# CONNECTOR_INTERFACE.net
KiCad netlist of a schematic drawn in Altium Designer
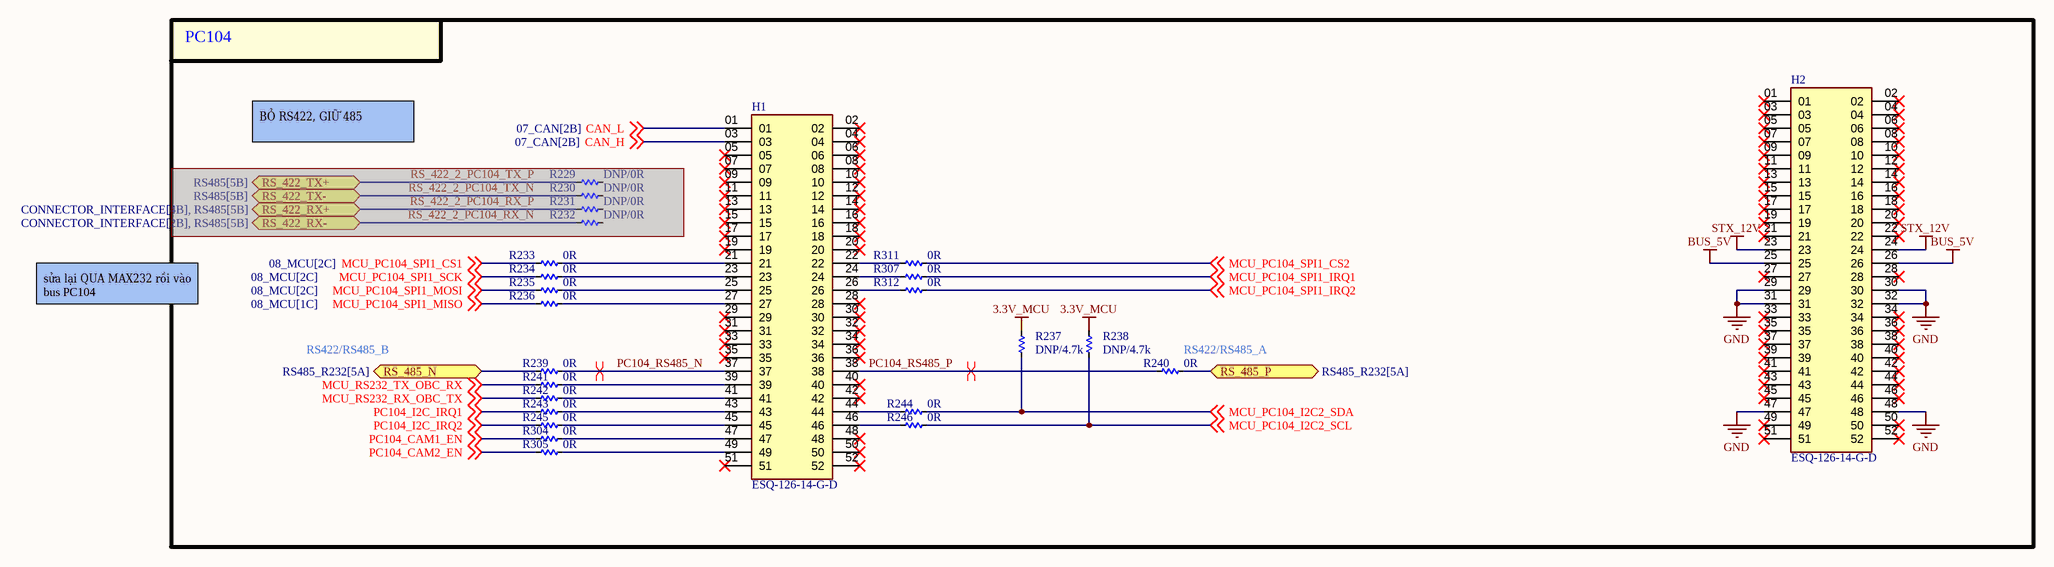
[diagram p0: CONNECTOR_INTERFACE.SchDoc]

(export (version "E")
  (design (tool "Eeschema 10.0.6"))
  (components
    (comp (ref "H1")
      (value "ESQ-126-14-G-D")
      (footprint "SAMTEC_ESQ-126-14-G-D")
      (description "CONN SOCKET 52POS 0.1 GOLD PCB")
      (fields (field (name "MF") "Samtec"))
      (libsource (lib "IFBschelib") (part "ESQ-126-14-G-D"))
    )
    (comp (ref "H2")
      (value "ESQ-126-14-G-D")
      (footprint "SAMTEC_ESQ-126-14-G-D")
      (description "CONN SOCKET 52POS 0.1 GOLD PCB")
      (fields (field (name "MF") "Samtec"))
      (libsource (lib "IFBschelib") (part "ESQ-126-14-G-D"))
    )
    (comp (ref "R229")
      (value "DNP/0R")
      (footprint "RES_C_1005x30_L")
      (description "RES")
      (libsource (lib "LABLIB") (part "_RES_B_2"))
    )
    (comp (ref "R230")
      (value "DNP/0R")
      (footprint "RES_C_1005x30_L")
      (description "RES")
      (libsource (lib "LABLIB") (part "_RES_B_2"))
    )
    (comp (ref "R231")
      (value "DNP/0R")
      (footprint "RES_C_1005x30_L")
      (description "RES")
      (libsource (lib "LABLIB") (part "_RES_B_2"))
    )
    (comp (ref "R232")
      (value "DNP/0R")
      (footprint "RES_C_1005x30_L")
      (description "RES")
      (libsource (lib "LABLIB") (part "_RES_B_2"))
    )
    (comp (ref "R233")
      (value "0R")
      (footprint "RES_C_1005x30_L")
      (description "RES")
      (libsource (lib "IFBschelib") (part "_RES_B_2"))
    )
    (comp (ref "R234")
      (value "0R")
      (footprint "RES_C_1005x30_L")
      (description "RES")
      (libsource (lib "IFBschelib") (part "_RES_B_2"))
    )
    (comp (ref "R235")
      (value "0R")
      (footprint "RES_C_1005x30_L")
      (description "RES")
      (libsource (lib "IFBschelib") (part "_RES_B_2"))
    )
    (comp (ref "R236")
      (value "0R")
      (footprint "RES_C_1005x30_L")
      (description "RES")
      (libsource (lib "IFBschelib") (part "_RES_B_2"))
    )
    (comp (ref "R237")
      (value "DNP/4.7k")
      (footprint "RES_C_1005x30_L")
      (description "RES")
      (libsource (lib "IFBschelib") (part "_RES_B_2"))
    )
    (comp (ref "R238")
      (value "DNP/4.7k")
      (footprint "RES_C_1005x30_L")
      (description "RES")
      (libsource (lib "IFBschelib") (part "_RES_B_2"))
    )
    (comp (ref "R239")
      (value "0R")
      (footprint "RES_C_1005x30_L")
      (description "RES")
      (libsource (lib "IFBschelib") (part "_RES_B_2"))
    )
    (comp (ref "R240")
      (value "0R")
      (footprint "RES_C_1005x30_L")
      (description "RES")
      (libsource (lib "IFBschelib") (part "_RES_B_2"))
    )
    (comp (ref "R241")
      (value "0R")
      (footprint "RES_C_1005x30_L")
      (description "RES")
      (libsource (lib "IFBschelib") (part "_RES_B_2"))
    )
    (comp (ref "R242")
      (value "0R")
      (footprint "RES_C_1005x30_L")
      (description "RES")
      (libsource (lib "IFBschelib") (part "_RES_B_2"))
    )
    (comp (ref "R243")
      (value "0R")
      (footprint "RES_C_1005x30_L")
      (description "RES")
      (libsource (lib "LABLIB") (part "_RES_B_2"))
    )
    (comp (ref "R244")
      (value "0R")
      (footprint "RES_C_1005x30_L")
      (description "RES")
      (libsource (lib "LABLIB") (part "_RES_B_2"))
    )
    (comp (ref "R245")
      (value "0R")
      (footprint "RES_C_1005x30_L")
      (description "RES")
      (libsource (lib "LABLIB") (part "_RES_B_2"))
    )
    (comp (ref "R246")
      (value "0R")
      (footprint "RES_C_1005x30_L")
      (description "RES")
      (libsource (lib "LABLIB") (part "_RES_B_2"))
    )
    (comp (ref "R304")
      (value "0R")
      (footprint "RES_C_1005x30_L")
      (description "RES")
      (libsource (lib "LABLIB") (part "_RES_B_2"))
    )
    (comp (ref "R305")
      (value "0R")
      (footprint "RES_C_1005x30_L")
      (description "RES")
      (libsource (lib "LABLIB") (part "_RES_B_2"))
    )
    (comp (ref "R307")
      (value "0R")
      (footprint "RES_C_1005x30_L")
      (description "RES")
      (libsource (lib "IFBschelib") (part "_RES_B_2"))
    )
    (comp (ref "R311")
      (value "0R")
      (footprint "RES_C_1005x30_L")
      (description "RES")
      (libsource (lib "IFBschelib") (part "_RES_B_2"))
    )
    (comp (ref "R312")
      (value "0R")
      (footprint "RES_C_1005x30_L")
      (description "RES")
      (libsource (lib "IFBschelib") (part "_RES_B_2"))
    )
  )
  (nets
    (net (code "1") (name "/PC104_RS485_N") (class "Default")
      (node (ref "H1") (pin "37") (pinfunction "37_37") (pintype "passive"))
      (node (ref "R239") (pin "2") (pinfunction "2_2") (pintype "passive"))
    )
    (net (code "2") (name "/PC104_RS485_P") (class "Default")
      (node (ref "H1") (pin "38") (pinfunction "38_38") (pintype "passive"))
      (node (ref "R240") (pin "1") (pinfunction "1_1") (pintype "passive"))
    )
    (net (code "3") (name "/RS_422_2_PC104_RX_N") (class "Default")
      (node (ref "R232") (pin "1") (pinfunction "1_1") (pintype "passive"))
    )
    (net (code "4") (name "/RS_422_2_PC104_RX_P") (class "Default")
      (node (ref "R231") (pin "1") (pinfunction "1_1") (pintype "passive"))
    )
    (net (code "5") (name "/RS_422_2_PC104_TX_N") (class "Default")
      (node (ref "R230") (pin "1") (pinfunction "1_1") (pintype "passive"))
    )
    (net (code "6") (name "/RS_422_2_PC104_TX_P") (class "Default")
      (node (ref "R229") (pin "1") (pinfunction "1_1") (pintype "passive"))
    )
    (net (code "7") (name "/RS_485_N") (class "Default")
      (node (ref "R239") (pin "1") (pinfunction "1_1") (pintype "passive"))
    )
    (net (code "8") (name "/RS_485_P") (class "Default")
      (node (ref "R240") (pin "2") (pinfunction "2_2") (pintype "passive"))
    )
    (net (code "9") (name "3.3V_MCU") (class "Default")
      (node (ref "R237") (pin "2") (pinfunction "2_2") (pintype "passive"))
      (node (ref "R238") (pin "2") (pinfunction "2_2") (pintype "passive"))
    )
    (net (code "10") (name "BUS_5V") (class "Default")
      (node (ref "H2") (pin "25") (pinfunction "25_25") (pintype "passive"))
      (node (ref "H2") (pin "26") (pinfunction "26_26") (pintype "passive"))
    )
    (net (code "11") (name "CAN_H") (class "Default")
      (node (ref "H1") (pin "03") (pinfunction "03_03") (pintype "passive"))
    )
    (net (code "12") (name "CAN_L") (class "Default")
      (node (ref "H1") (pin "01") (pinfunction "01_01") (pintype "passive"))
    )
    (net (code "13") (name "GND") (class "Default")
      (node (ref "H2") (pin "29") (pinfunction "29_29") (pintype "passive"))
      (node (ref "H2") (pin "30") (pinfunction "30_30") (pintype "passive"))
      (node (ref "H2") (pin "31") (pinfunction "31_31") (pintype "passive"))
      (node (ref "H2") (pin "32") (pinfunction "32_32") (pintype "passive"))
      (node (ref "H2") (pin "47") (pinfunction "47_47") (pintype "passive"))
      (node (ref "H2") (pin "48") (pinfunction "48_48") (pintype "passive"))
    )
    (net (code "14") (name "MCU_PC104_I2C2_SCL") (class "Default")
      (node (ref "R238") (pin "1") (pinfunction "1_1") (pintype "passive"))
      (node (ref "R246") (pin "2") (pinfunction "2_2") (pintype "passive"))
    )
    (net (code "15") (name "MCU_PC104_I2C2_SDA") (class "Default")
      (node (ref "R237") (pin "1") (pinfunction "1_1") (pintype "passive"))
      (node (ref "R244") (pin "2") (pinfunction "2_2") (pintype "passive"))
    )
    (net (code "16") (name "MCU_PC104_SPI1_CS1") (class "Default")
      (node (ref "R233") (pin "1") (pinfunction "1_1") (pintype "passive"))
    )
    (net (code "17") (name "MCU_PC104_SPI1_CS2") (class "Default")
      (node (ref "R311") (pin "1") (pinfunction "1_1") (pintype "passive"))
    )
    (net (code "18") (name "MCU_PC104_SPI1_IRQ1") (class "Default")
      (node (ref "R307") (pin "2") (pinfunction "2_2") (pintype "passive"))
    )
    (net (code "19") (name "MCU_PC104_SPI1_IRQ2") (class "Default")
      (node (ref "R312") (pin "2") (pinfunction "2_2") (pintype "passive"))
    )
    (net (code "20") (name "MCU_PC104_SPI1_MISO") (class "Default")
      (node (ref "R236") (pin "1") (pinfunction "1_1") (pintype "passive"))
    )
    (net (code "21") (name "MCU_PC104_SPI1_MOSI") (class "Default")
      (node (ref "R235") (pin "1") (pinfunction "1_1") (pintype "passive"))
    )
    (net (code "22") (name "MCU_PC104_SPI1_SCK") (class "Default")
      (node (ref "R234") (pin "1") (pinfunction "1_1") (pintype "passive"))
    )
    (net (code "23") (name "MCU_RS232_RX_OBC_TX") (class "Default")
      (node (ref "R242") (pin "1") (pinfunction "1_1") (pintype "passive"))
    )
    (net (code "24") (name "MCU_RS232_TX_OBC_RX") (class "Default")
      (node (ref "R241") (pin "1") (pinfunction "1_1") (pintype "passive"))
    )
    (net (code "25") (name "Net-(H1-Pad21)") (class "Default")
      (node (ref "H1") (pin "21") (pinfunction "21_21") (pintype "passive"))
      (node (ref "R233") (pin "2") (pinfunction "2_2") (pintype "passive"))
    )
    (net (code "26") (name "Net-(H1-Pad22)") (class "Default")
      (node (ref "H1") (pin "22") (pinfunction "22_22") (pintype "passive"))
      (node (ref "R311") (pin "2") (pinfunction "2_2") (pintype "passive"))
    )
    (net (code "27") (name "Net-(H1-Pad23)") (class "Default")
      (node (ref "H1") (pin "23") (pinfunction "23_23") (pintype "passive"))
      (node (ref "R234") (pin "2") (pinfunction "2_2") (pintype "passive"))
    )
    (net (code "28") (name "Net-(H1-Pad24)") (class "Default")
      (node (ref "H1") (pin "24") (pinfunction "24_24") (pintype "passive"))
      (node (ref "R307") (pin "1") (pinfunction "1_1") (pintype "passive"))
    )
    (net (code "29") (name "Net-(H1-Pad25)") (class "Default")
      (node (ref "H1") (pin "25") (pinfunction "25_25") (pintype "passive"))
      (node (ref "R235") (pin "2") (pinfunction "2_2") (pintype "passive"))
    )
    (net (code "30") (name "Net-(H1-Pad26)") (class "Default")
      (node (ref "H1") (pin "26") (pinfunction "26_26") (pintype "passive"))
      (node (ref "R312") (pin "1") (pinfunction "1_1") (pintype "passive"))
    )
    (net (code "31") (name "Net-(H1-Pad27)") (class "Default")
      (node (ref "H1") (pin "27") (pinfunction "27_27") (pintype "passive"))
      (node (ref "R236") (pin "2") (pinfunction "2_2") (pintype "passive"))
    )
    (net (code "32") (name "Net-(H1-Pad39)") (class "Default")
      (node (ref "H1") (pin "39") (pinfunction "39_39") (pintype "passive"))
      (node (ref "R241") (pin "2") (pinfunction "2_2") (pintype "passive"))
    )
    (net (code "33") (name "Net-(H1-Pad41)") (class "Default")
      (node (ref "H1") (pin "41") (pinfunction "41_41") (pintype "passive"))
      (node (ref "R242") (pin "2") (pinfunction "2_2") (pintype "passive"))
    )
    (net (code "34") (name "Net-(H1-Pad43)") (class "Default")
      (node (ref "H1") (pin "43") (pinfunction "43_43") (pintype "passive"))
      (node (ref "R243") (pin "2") (pinfunction "2_2") (pintype "passive"))
    )
    (net (code "35") (name "Net-(H1-Pad44)") (class "Default")
      (node (ref "H1") (pin "44") (pinfunction "44_44") (pintype "passive"))
      (node (ref "R244") (pin "1") (pinfunction "1_1") (pintype "passive"))
    )
    (net (code "36") (name "Net-(H1-Pad45)") (class "Default")
      (node (ref "H1") (pin "45") (pinfunction "45_45") (pintype "passive"))
      (node (ref "R245") (pin "2") (pinfunction "2_2") (pintype "passive"))
    )
    (net (code "37") (name "Net-(H1-Pad46)") (class "Default")
      (node (ref "H1") (pin "46") (pinfunction "46_46") (pintype "passive"))
      (node (ref "R246") (pin "1") (pinfunction "1_1") (pintype "passive"))
    )
    (net (code "38") (name "Net-(H1-Pad47)") (class "Default")
      (node (ref "H1") (pin "47") (pinfunction "47_47") (pintype "passive"))
      (node (ref "R304") (pin "2") (pinfunction "2_2") (pintype "passive"))
    )
    (net (code "39") (name "Net-(H1-Pad49)") (class "Default")
      (node (ref "H1") (pin "49") (pinfunction "49_49") (pintype "passive"))
      (node (ref "R305") (pin "2") (pinfunction "2_2") (pintype "passive"))
    )
    (net (code "40") (name "PC104_CAM1_EN") (class "Default")
      (node (ref "R304") (pin "1") (pinfunction "1_1") (pintype "passive"))
    )
    (net (code "41") (name "PC104_CAM2_EN") (class "Default")
      (node (ref "R305") (pin "1") (pinfunction "1_1") (pintype "passive"))
    )
    (net (code "42") (name "PC104_I2C_IRQ1") (class "Default")
      (node (ref "R243") (pin "1") (pinfunction "1_1") (pintype "passive"))
    )
    (net (code "43") (name "PC104_I2C_IRQ2") (class "Default")
      (node (ref "R245") (pin "1") (pinfunction "1_1") (pintype "passive"))
    )
    (net (code "44") (name "STX_12V") (class "Default")
      (node (ref "H2") (pin "23") (pinfunction "23_23") (pintype "passive"))
      (node (ref "H2") (pin "24") (pinfunction "24_24") (pintype "passive"))
    )
    (net (code "45") (name "unconnected-(H1-Pad02)") (class "Default")
      (node (ref "H1") (pin "02") (pinfunction "02_02") (pintype "passive+no_connect"))
    )
    (net (code "46") (name "unconnected-(H1-Pad04)") (class "Default")
      (node (ref "H1") (pin "04") (pinfunction "04_04") (pintype "passive+no_connect"))
    )
    (net (code "47") (name "unconnected-(H1-Pad05)") (class "Default")
      (node (ref "H1") (pin "05") (pinfunction "05_05") (pintype "passive+no_connect"))
    )
    (net (code "48") (name "unconnected-(H1-Pad06)") (class "Default")
      (node (ref "H1") (pin "06") (pinfunction "06_06") (pintype "passive+no_connect"))
    )
    (net (code "49") (name "unconnected-(H1-Pad07)") (class "Default")
      (node (ref "H1") (pin "07") (pinfunction "07_07") (pintype "passive+no_connect"))
    )
    (net (code "50") (name "unconnected-(H1-Pad08)") (class "Default")
      (node (ref "H1") (pin "08") (pinfunction "08_08") (pintype "passive+no_connect"))
    )
    (net (code "51") (name "unconnected-(H1-Pad09)") (class "Default")
      (node (ref "H1") (pin "09") (pinfunction "09_09") (pintype "passive+no_connect"))
    )
    (net (code "52") (name "unconnected-(H1-Pad10)") (class "Default")
      (node (ref "H1") (pin "10") (pinfunction "10_10") (pintype "passive+no_connect"))
    )
    (net (code "53") (name "unconnected-(H1-Pad11)") (class "Default")
      (node (ref "H1") (pin "11") (pinfunction "11_11") (pintype "passive+no_connect"))
    )
    (net (code "54") (name "unconnected-(H1-Pad12)") (class "Default")
      (node (ref "H1") (pin "12") (pinfunction "12_12") (pintype "passive+no_connect"))
    )
    (net (code "55") (name "unconnected-(H1-Pad13)") (class "Default")
      (node (ref "H1") (pin "13") (pinfunction "13_13") (pintype "passive+no_connect"))
    )
    (net (code "56") (name "unconnected-(H1-Pad14)") (class "Default")
      (node (ref "H1") (pin "14") (pinfunction "14_14") (pintype "passive+no_connect"))
    )
    (net (code "57") (name "unconnected-(H1-Pad15)") (class "Default")
      (node (ref "H1") (pin "15") (pinfunction "15_15") (pintype "passive+no_connect"))
    )
    (net (code "58") (name "unconnected-(H1-Pad16)") (class "Default")
      (node (ref "H1") (pin "16") (pinfunction "16_16") (pintype "passive+no_connect"))
    )
    (net (code "59") (name "unconnected-(H1-Pad17)") (class "Default")
      (node (ref "H1") (pin "17") (pinfunction "17_17") (pintype "passive+no_connect"))
    )
    (net (code "60") (name "unconnected-(H1-Pad18)") (class "Default")
      (node (ref "H1") (pin "18") (pinfunction "18_18") (pintype "passive+no_connect"))
    )
    (net (code "61") (name "unconnected-(H1-Pad19)") (class "Default")
      (node (ref "H1") (pin "19") (pinfunction "19_19") (pintype "passive+no_connect"))
    )
    (net (code "62") (name "unconnected-(H1-Pad20)") (class "Default")
      (node (ref "H1") (pin "20") (pinfunction "20_20") (pintype "passive+no_connect"))
    )
    (net (code "63") (name "unconnected-(H1-Pad28)") (class "Default")
      (node (ref "H1") (pin "28") (pinfunction "28_28") (pintype "passive+no_connect"))
    )
    (net (code "64") (name "unconnected-(H1-Pad29)") (class "Default")
      (node (ref "H1") (pin "29") (pinfunction "29_29") (pintype "passive+no_connect"))
    )
    (net (code "65") (name "unconnected-(H1-Pad30)") (class "Default")
      (node (ref "H1") (pin "30") (pinfunction "30_30") (pintype "passive+no_connect"))
    )
    (net (code "66") (name "unconnected-(H1-Pad31)") (class "Default")
      (node (ref "H1") (pin "31") (pinfunction "31_31") (pintype "passive+no_connect"))
    )
    (net (code "67") (name "unconnected-(H1-Pad32)") (class "Default")
      (node (ref "H1") (pin "32") (pinfunction "32_32") (pintype "passive+no_connect"))
    )
    (net (code "68") (name "unconnected-(H1-Pad33)") (class "Default")
      (node (ref "H1") (pin "33") (pinfunction "33_33") (pintype "passive+no_connect"))
    )
    (net (code "69") (name "unconnected-(H1-Pad34)") (class "Default")
      (node (ref "H1") (pin "34") (pinfunction "34_34") (pintype "passive+no_connect"))
    )
    (net (code "70") (name "unconnected-(H1-Pad35)") (class "Default")
      (node (ref "H1") (pin "35") (pinfunction "35_35") (pintype "passive+no_connect"))
    )
    (net (code "71") (name "unconnected-(H1-Pad36)") (class "Default")
      (node (ref "H1") (pin "36") (pinfunction "36_36") (pintype "passive+no_connect"))
    )
    (net (code "72") (name "unconnected-(H1-Pad40)") (class "Default")
      (node (ref "H1") (pin "40") (pinfunction "40_40") (pintype "passive+no_connect"))
    )
    (net (code "73") (name "unconnected-(H1-Pad42)") (class "Default")
      (node (ref "H1") (pin "42") (pinfunction "42_42") (pintype "passive+no_connect"))
    )
    (net (code "74") (name "unconnected-(H1-Pad48)") (class "Default")
      (node (ref "H1") (pin "48") (pinfunction "48_48") (pintype "passive+no_connect"))
    )
    (net (code "75") (name "unconnected-(H1-Pad50)") (class "Default")
      (node (ref "H1") (pin "50") (pinfunction "50_50") (pintype "passive+no_connect"))
    )
    (net (code "76") (name "unconnected-(H1-Pad51)") (class "Default")
      (node (ref "H1") (pin "51") (pinfunction "51_51") (pintype "passive+no_connect"))
    )
    (net (code "77") (name "unconnected-(H1-Pad52)") (class "Default")
      (node (ref "H1") (pin "52") (pinfunction "52_52") (pintype "passive+no_connect"))
    )
    (net (code "78") (name "unconnected-(H2-Pad01)") (class "Default")
      (node (ref "H2") (pin "01") (pinfunction "01_01") (pintype "passive+no_connect"))
    )
    (net (code "79") (name "unconnected-(H2-Pad02)") (class "Default")
      (node (ref "H2") (pin "02") (pinfunction "02_02") (pintype "passive+no_connect"))
    )
    (net (code "80") (name "unconnected-(H2-Pad03)") (class "Default")
      (node (ref "H2") (pin "03") (pinfunction "03_03") (pintype "passive+no_connect"))
    )
    (net (code "81") (name "unconnected-(H2-Pad04)") (class "Default")
      (node (ref "H2") (pin "04") (pinfunction "04_04") (pintype "passive+no_connect"))
    )
    (net (code "82") (name "unconnected-(H2-Pad05)") (class "Default")
      (node (ref "H2") (pin "05") (pinfunction "05_05") (pintype "passive+no_connect"))
    )
    (net (code "83") (name "unconnected-(H2-Pad06)") (class "Default")
      (node (ref "H2") (pin "06") (pinfunction "06_06") (pintype "passive+no_connect"))
    )
    (net (code "84") (name "unconnected-(H2-Pad07)") (class "Default")
      (node (ref "H2") (pin "07") (pinfunction "07_07") (pintype "passive+no_connect"))
    )
    (net (code "85") (name "unconnected-(H2-Pad08)") (class "Default")
      (node (ref "H2") (pin "08") (pinfunction "08_08") (pintype "passive+no_connect"))
    )
    (net (code "86") (name "unconnected-(H2-Pad09)") (class "Default")
      (node (ref "H2") (pin "09") (pinfunction "09_09") (pintype "passive+no_connect"))
    )
    (net (code "87") (name "unconnected-(H2-Pad10)") (class "Default")
      (node (ref "H2") (pin "10") (pinfunction "10_10") (pintype "passive+no_connect"))
    )
    (net (code "88") (name "unconnected-(H2-Pad11)") (class "Default")
      (node (ref "H2") (pin "11") (pinfunction "11_11") (pintype "passive+no_connect"))
    )
    (net (code "89") (name "unconnected-(H2-Pad12)") (class "Default")
      (node (ref "H2") (pin "12") (pinfunction "12_12") (pintype "passive+no_connect"))
    )
    (net (code "90") (name "unconnected-(H2-Pad13)") (class "Default")
      (node (ref "H2") (pin "13") (pinfunction "13_13") (pintype "passive+no_connect"))
    )
    (net (code "91") (name "unconnected-(H2-Pad14)") (class "Default")
      (node (ref "H2") (pin "14") (pinfunction "14_14") (pintype "passive+no_connect"))
    )
    (net (code "92") (name "unconnected-(H2-Pad15)") (class "Default")
      (node (ref "H2") (pin "15") (pinfunction "15_15") (pintype "passive+no_connect"))
    )
    (net (code "93") (name "unconnected-(H2-Pad16)") (class "Default")
      (node (ref "H2") (pin "16") (pinfunction "16_16") (pintype "passive+no_connect"))
    )
    (net (code "94") (name "unconnected-(H2-Pad17)") (class "Default")
      (node (ref "H2") (pin "17") (pinfunction "17_17") (pintype "passive+no_connect"))
    )
    (net (code "95") (name "unconnected-(H2-Pad18)") (class "Default")
      (node (ref "H2") (pin "18") (pinfunction "18_18") (pintype "passive+no_connect"))
    )
    (net (code "96") (name "unconnected-(H2-Pad19)") (class "Default")
      (node (ref "H2") (pin "19") (pinfunction "19_19") (pintype "passive+no_connect"))
    )
    (net (code "97") (name "unconnected-(H2-Pad20)") (class "Default")
      (node (ref "H2") (pin "20") (pinfunction "20_20") (pintype "passive+no_connect"))
    )
    (net (code "98") (name "unconnected-(H2-Pad21)") (class "Default")
      (node (ref "H2") (pin "21") (pinfunction "21_21") (pintype "passive+no_connect"))
    )
    (net (code "99") (name "unconnected-(H2-Pad22)") (class "Default")
      (node (ref "H2") (pin "22") (pinfunction "22_22") (pintype "passive+no_connect"))
    )
    (net (code "100") (name "unconnected-(H2-Pad27)") (class "Default")
      (node (ref "H2") (pin "27") (pinfunction "27_27") (pintype "passive+no_connect"))
    )
    (net (code "101") (name "unconnected-(H2-Pad28)") (class "Default")
      (node (ref "H2") (pin "28") (pinfunction "28_28") (pintype "passive+no_connect"))
    )
    (net (code "102") (name "unconnected-(H2-Pad33)") (class "Default")
      (node (ref "H2") (pin "33") (pinfunction "33_33") (pintype "passive+no_connect"))
    )
    (net (code "103") (name "unconnected-(H2-Pad34)") (class "Default")
      (node (ref "H2") (pin "34") (pinfunction "34_34") (pintype "passive+no_connect"))
    )
    (net (code "104") (name "unconnected-(H2-Pad35)") (class "Default")
      (node (ref "H2") (pin "35") (pinfunction "35_35") (pintype "passive+no_connect"))
    )
    (net (code "105") (name "unconnected-(H2-Pad36)") (class "Default")
      (node (ref "H2") (pin "36") (pinfunction "36_36") (pintype "passive+no_connect"))
    )
    (net (code "106") (name "unconnected-(H2-Pad37)") (class "Default")
      (node (ref "H2") (pin "37") (pinfunction "37_37") (pintype "passive+no_connect"))
    )
    (net (code "107") (name "unconnected-(H2-Pad38)") (class "Default")
      (node (ref "H2") (pin "38") (pinfunction "38_38") (pintype "passive+no_connect"))
    )
    (net (code "108") (name "unconnected-(H2-Pad39)") (class "Default")
      (node (ref "H2") (pin "39") (pinfunction "39_39") (pintype "passive+no_connect"))
    )
    (net (code "109") (name "unconnected-(H2-Pad40)") (class "Default")
      (node (ref "H2") (pin "40") (pinfunction "40_40") (pintype "passive+no_connect"))
    )
    (net (code "110") (name "unconnected-(H2-Pad41)") (class "Default")
      (node (ref "H2") (pin "41") (pinfunction "41_41") (pintype "passive+no_connect"))
    )
    (net (code "111") (name "unconnected-(H2-Pad42)") (class "Default")
      (node (ref "H2") (pin "42") (pinfunction "42_42") (pintype "passive+no_connect"))
    )
    (net (code "112") (name "unconnected-(H2-Pad43)") (class "Default")
      (node (ref "H2") (pin "43") (pinfunction "43_43") (pintype "passive+no_connect"))
    )
    (net (code "113") (name "unconnected-(H2-Pad44)") (class "Default")
      (node (ref "H2") (pin "44") (pinfunction "44_44") (pintype "passive+no_connect"))
    )
    (net (code "114") (name "unconnected-(H2-Pad45)") (class "Default")
      (node (ref "H2") (pin "45") (pinfunction "45_45") (pintype "passive+no_connect"))
    )
    (net (code "115") (name "unconnected-(H2-Pad46)") (class "Default")
      (node (ref "H2") (pin "46") (pinfunction "46_46") (pintype "passive+no_connect"))
    )
    (net (code "116") (name "unconnected-(H2-Pad49)") (class "Default")
      (node (ref "H2") (pin "49") (pinfunction "49_49") (pintype "passive+no_connect"))
    )
    (net (code "117") (name "unconnected-(H2-Pad50)") (class "Default")
      (node (ref "H2") (pin "50") (pinfunction "50_50") (pintype "passive+no_connect"))
    )
    (net (code "118") (name "unconnected-(H2-Pad51)") (class "Default")
      (node (ref "H2") (pin "51") (pinfunction "51_51") (pintype "passive+no_connect"))
    )
    (net (code "119") (name "unconnected-(H2-Pad52)") (class "Default")
      (node (ref "H2") (pin "52") (pinfunction "52_52") (pintype "passive+no_connect"))
    )
    (net (code "120") (name "unconnected-(R229-Pad2)") (class "Default")
      (node (ref "R229") (pin "2") (pinfunction "2_2") (pintype "passive"))
    )
    (net (code "121") (name "unconnected-(R230-Pad2)") (class "Default")
      (node (ref "R230") (pin "2") (pinfunction "2_2") (pintype "passive"))
    )
    (net (code "122") (name "unconnected-(R231-Pad2)") (class "Default")
      (node (ref "R231") (pin "2") (pinfunction "2_2") (pintype "passive"))
    )
    (net (code "123") (name "unconnected-(R232-Pad2)") (class "Default")
      (node (ref "R232") (pin "2") (pinfunction "2_2") (pintype "passive"))
    )
  )
)
